# Debug.net
KiCad netlist of a schematic drawn in Altium Designer
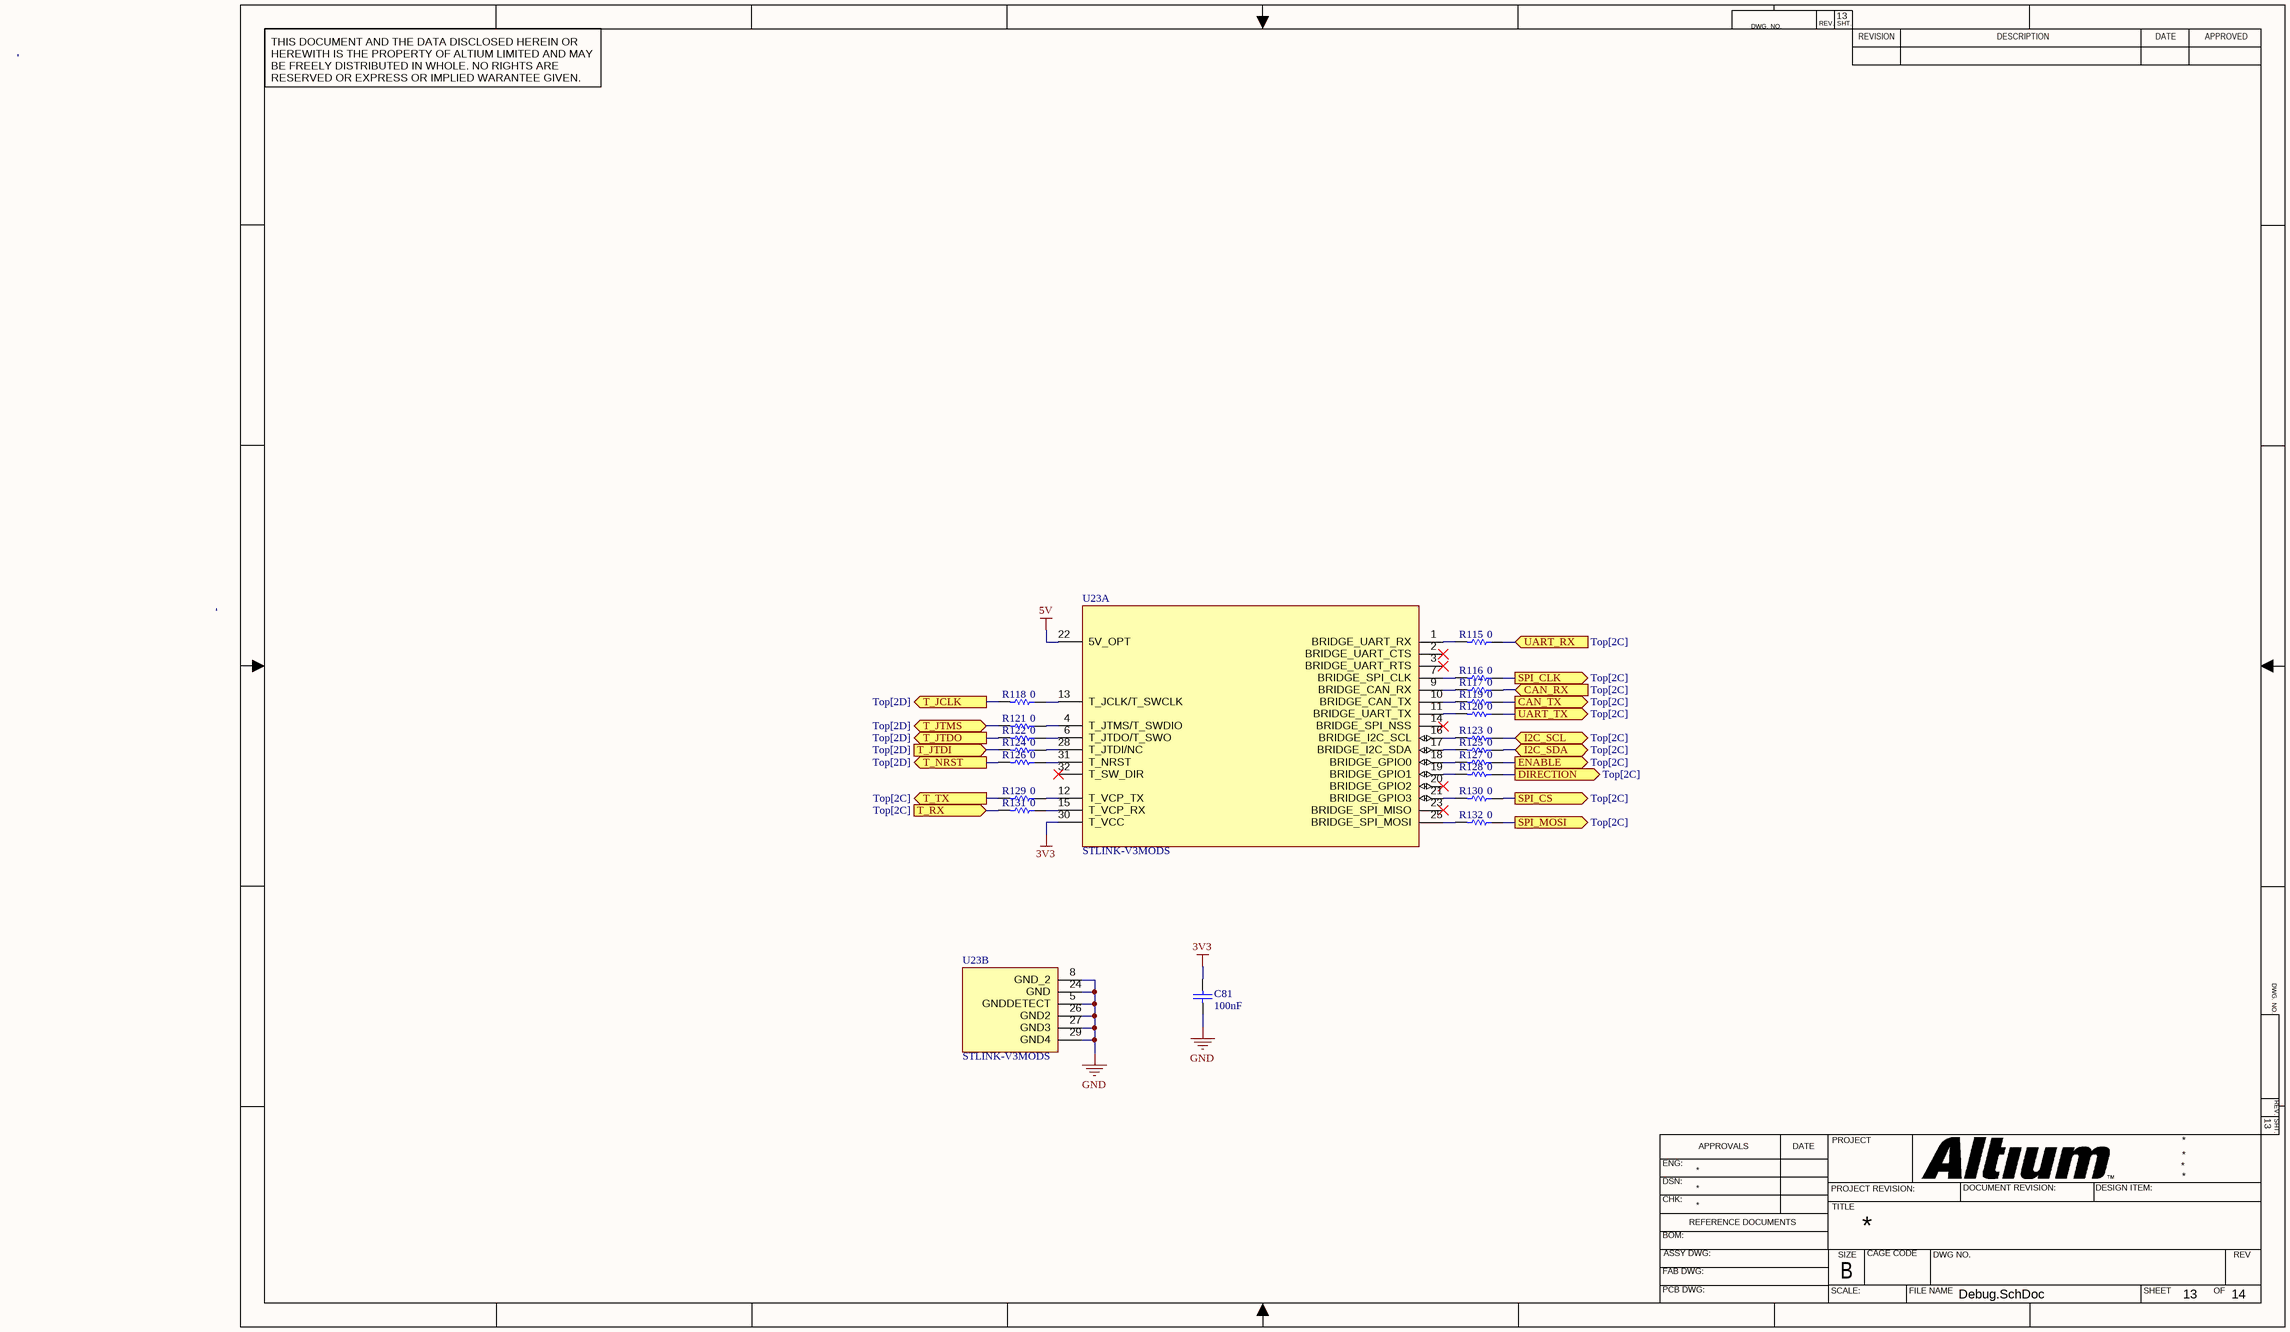
[diagram p0: Debug.SchDoc]

(export (version "E")
  (design (tool "Eeschema 10.0.6"))
  (components
    (comp (ref "C81")
      (value "100nF")
      (description "Capacitor")
      (libsource (lib "Simulation Generic Components") (part "Capacitor"))
    )
    (comp (ref "R115")
      (value "0")
      (description "Resistor")
      (libsource (lib "Simulation Generic Components") (part "Resistor"))
    )
    (comp (ref "R116")
      (value "0")
      (description "Resistor")
      (libsource (lib "Simulation Generic Components") (part "Resistor"))
    )
    (comp (ref "R117")
      (value "0")
      (description "Resistor")
      (libsource (lib "Simulation Generic Components") (part "Resistor"))
    )
    (comp (ref "R118")
      (value "0")
      (description "Resistor")
      (libsource (lib "Simulation Generic Components") (part "Resistor"))
    )
    (comp (ref "R119")
      (value "0")
      (description "Resistor")
      (libsource (lib "Simulation Generic Components") (part "Resistor"))
    )
    (comp (ref "R120")
      (value "0")
      (description "Resistor")
      (libsource (lib "Simulation Generic Components") (part "Resistor"))
    )
    (comp (ref "R121")
      (value "0")
      (description "Resistor")
      (libsource (lib "Simulation Generic Components") (part "Resistor"))
    )
    (comp (ref "R122")
      (value "0")
      (description "Resistor")
      (libsource (lib "Simulation Generic Components") (part "Resistor"))
    )
    (comp (ref "R123")
      (value "0")
      (description "Resistor")
      (libsource (lib "Simulation Generic Components") (part "Resistor"))
    )
    (comp (ref "R124")
      (value "0")
      (description "Resistor")
      (libsource (lib "Simulation Generic Components") (part "Resistor"))
    )
    (comp (ref "R125")
      (value "0")
      (description "Resistor")
      (libsource (lib "Simulation Generic Components") (part "Resistor"))
    )
    (comp (ref "R126")
      (value "0")
      (description "Resistor")
      (libsource (lib "Simulation Generic Components") (part "Resistor"))
    )
    (comp (ref "R127")
      (value "0")
      (description "Resistor")
      (libsource (lib "Simulation Generic Components") (part "Resistor"))
    )
    (comp (ref "R128")
      (value "0")
      (description "Resistor")
      (libsource (lib "Simulation Generic Components") (part "Resistor"))
    )
    (comp (ref "R129")
      (value "0")
      (description "Resistor")
      (libsource (lib "Simulation Generic Components") (part "Resistor"))
    )
    (comp (ref "R130")
      (value "0")
      (description "Resistor")
      (libsource (lib "Simulation Generic Components") (part "Resistor"))
    )
    (comp (ref "R131")
      (value "0")
      (description "Resistor")
      (libsource (lib "Simulation Generic Components") (part "Resistor"))
    )
    (comp (ref "R132")
      (value "0")
      (description "Resistor")
      (libsource (lib "Simulation Generic Components") (part "Resistor"))
    )
    (comp (ref "U23")
      (value "STLINK-V3MODS")
      (footprint "MODULE_STLINK-V3MODS")
      (libsource (lib "GSSM Golf Cart") (part "STLINK-V3MODS"))
    )
  )
  (nets
    (net (code "1") (name "/CAN_RX") (class "Default")
      (node (ref "R117") (pin "1") (pinfunction "1_1") (pintype "passive"))
    )
    (net (code "2") (name "/CAN_TX") (class "Default")
      (node (ref "R119") (pin "1") (pinfunction "1_1") (pintype "passive"))
    )
    (net (code "3") (name "/DIRECTION") (class "Default")
      (node (ref "R128") (pin "1") (pinfunction "1_1") (pintype "passive"))
    )
    (net (code "4") (name "/ENABLE") (class "Default")
      (node (ref "R127") (pin "1") (pinfunction "1_1") (pintype "passive"))
    )
    (net (code "5") (name "/I2C_SCL") (class "Default")
      (node (ref "R123") (pin "1") (pinfunction "1_1") (pintype "passive"))
    )
    (net (code "6") (name "/I2C_SDA") (class "Default")
      (node (ref "R125") (pin "1") (pinfunction "1_1") (pintype "passive"))
    )
    (net (code "7") (name "/SPI_CLK") (class "Default")
      (node (ref "R116") (pin "1") (pinfunction "1_1") (pintype "passive"))
    )
    (net (code "8") (name "/SPI_CS") (class "Default")
      (node (ref "R130") (pin "1") (pinfunction "1_1") (pintype "passive"))
    )
    (net (code "9") (name "/SPI_MOSI") (class "Default")
      (node (ref "R132") (pin "1") (pinfunction "1_1") (pintype "passive"))
    )
    (net (code "10") (name "/T_JCLK") (class "Default")
      (node (ref "R118") (pin "2") (pinfunction "2_2") (pintype "passive"))
    )
    (net (code "11") (name "/T_JTDI") (class "Default")
      (node (ref "R124") (pin "2") (pinfunction "2_2") (pintype "passive"))
    )
    (net (code "12") (name "/T_JTDO") (class "Default")
      (node (ref "R122") (pin "2") (pinfunction "2_2") (pintype "passive"))
    )
    (net (code "13") (name "/T_JTMS") (class "Default")
      (node (ref "R121") (pin "2") (pinfunction "2_2") (pintype "passive"))
    )
    (net (code "14") (name "/T_NRST") (class "Default")
      (node (ref "R126") (pin "2") (pinfunction "2_2") (pintype "passive"))
    )
    (net (code "15") (name "/T_RX") (class "Default")
      (node (ref "R131") (pin "2") (pinfunction "2_2") (pintype "passive"))
    )
    (net (code "16") (name "/T_TX") (class "Default")
      (node (ref "R129") (pin "2") (pinfunction "2_2") (pintype "passive"))
    )
    (net (code "17") (name "/UART_RX") (class "Default")
      (node (ref "R115") (pin "1") (pinfunction "1_1") (pintype "passive"))
    )
    (net (code "18") (name "/UART_TX") (class "Default")
      (node (ref "R120") (pin "1") (pinfunction "1_1") (pintype "passive"))
    )
    (net (code "19") (name "3V3") (class "Default")
      (node (ref "C81") (pin "2") (pinfunction "2_2") (pintype "passive"))
      (node (ref "U23") (pin "30") (pinfunction "T_VCC_30") (pintype "passive"))
    )
    (net (code "20") (name "5V") (class "Default")
      (node (ref "U23") (pin "22") (pinfunction "5V_OPT_22") (pintype "passive"))
    )
    (net (code "21") (name "GND") (class "Default")
      (node (ref "C81") (pin "1") (pinfunction "1_1") (pintype "passive"))
      (node (ref "U23") (pin "24") (pinfunction "GND_24") (pintype "power_in"))
      (node (ref "U23") (pin "26") (pinfunction "GND2_26") (pintype "power_in"))
      (node (ref "U23") (pin "27") (pinfunction "GND3_27") (pintype "power_in"))
      (node (ref "U23") (pin "29") (pinfunction "GND4_29") (pintype "power_in"))
      (node (ref "U23") (pin "5") (pinfunction "GNDDETECT_5") (pintype "power_in"))
      (node (ref "U23") (pin "8") (pinfunction "GND_2_8") (pintype "power_in"))
    )
    (net (code "22") (name "Net-(U23A-BRIDGE_CAN_RX)") (class "Default")
      (node (ref "R117") (pin "2") (pinfunction "2_2") (pintype "passive"))
      (node (ref "U23") (pin "9") (pinfunction "BRIDGE_CAN_RX_9") (pintype "passive"))
    )
    (net (code "23") (name "Net-(U23A-BRIDGE_CAN_TX)") (class "Default")
      (node (ref "R119") (pin "2") (pinfunction "2_2") (pintype "passive"))
      (node (ref "U23") (pin "10") (pinfunction "BRIDGE_CAN_TX_10") (pintype "passive"))
    )
    (net (code "24") (name "Net-(U23A-BRIDGE_GPIO0)") (class "Default")
      (node (ref "R127") (pin "2") (pinfunction "2_2") (pintype "passive"))
      (node (ref "U23") (pin "18") (pinfunction "BRIDGE_GPIO0_18") (pintype "bidirectional"))
    )
    (net (code "25") (name "Net-(U23A-BRIDGE_GPIO1)") (class "Default")
      (node (ref "R128") (pin "2") (pinfunction "2_2") (pintype "passive"))
      (node (ref "U23") (pin "19") (pinfunction "BRIDGE_GPIO1_19") (pintype "bidirectional"))
    )
    (net (code "26") (name "Net-(U23A-BRIDGE_GPIO3)") (class "Default")
      (node (ref "R130") (pin "2") (pinfunction "2_2") (pintype "passive"))
      (node (ref "U23") (pin "21") (pinfunction "BRIDGE_GPIO3_21") (pintype "bidirectional"))
    )
    (net (code "27") (name "Net-(U23A-BRIDGE_I2C_SCL)") (class "Default")
      (node (ref "R123") (pin "2") (pinfunction "2_2") (pintype "passive"))
      (node (ref "U23") (pin "16") (pinfunction "BRIDGE_I2C_SCL_16") (pintype "bidirectional"))
    )
    (net (code "28") (name "Net-(U23A-BRIDGE_I2C_SDA)") (class "Default")
      (node (ref "R125") (pin "2") (pinfunction "2_2") (pintype "passive"))
      (node (ref "U23") (pin "17") (pinfunction "BRIDGE_I2C_SDA_17") (pintype "bidirectional"))
    )
    (net (code "29") (name "Net-(U23A-BRIDGE_SPI_CLK)") (class "Default")
      (node (ref "R116") (pin "2") (pinfunction "2_2") (pintype "passive"))
      (node (ref "U23") (pin "7") (pinfunction "BRIDGE_SPI_CLK_7") (pintype "passive"))
    )
    (net (code "30") (name "Net-(U23A-BRIDGE_SPI_MOSI)") (class "Default")
      (node (ref "R132") (pin "2") (pinfunction "2_2") (pintype "passive"))
      (node (ref "U23") (pin "25") (pinfunction "BRIDGE_SPI_MOSI_25") (pintype "passive"))
    )
    (net (code "31") (name "Net-(U23A-BRIDGE_UART_RX)") (class "Default")
      (node (ref "R115") (pin "2") (pinfunction "2_2") (pintype "passive"))
      (node (ref "U23") (pin "1") (pinfunction "BRIDGE_UART_RX_1") (pintype "passive"))
    )
    (net (code "32") (name "Net-(U23A-BRIDGE_UART_TX)") (class "Default")
      (node (ref "R120") (pin "2") (pinfunction "2_2") (pintype "passive"))
      (node (ref "U23") (pin "11") (pinfunction "BRIDGE_UART_TX_11") (pintype "passive"))
    )
    (net (code "33") (name "Net-(U23A-T_JCLK{slash}T_SWCLK)") (class "Default")
      (node (ref "R118") (pin "1") (pinfunction "1_1") (pintype "passive"))
      (node (ref "U23") (pin "13") (pinfunction "T_JCLK/T_SWCLK_13") (pintype "passive"))
    )
    (net (code "34") (name "Net-(U23A-T_JTDI{slash}NC)") (class "Default")
      (node (ref "R124") (pin "1") (pinfunction "1_1") (pintype "passive"))
      (node (ref "U23") (pin "28") (pinfunction "T_JTDI/NC_28") (pintype "passive"))
    )
    (net (code "35") (name "Net-(U23A-T_JTDO{slash}T_SWO)") (class "Default")
      (node (ref "R122") (pin "1") (pinfunction "1_1") (pintype "passive"))
      (node (ref "U23") (pin "6") (pinfunction "T_JTDO/T_SWO_6") (pintype "passive"))
    )
    (net (code "36") (name "Net-(U23A-T_JTMS{slash}T_SWDIO)") (class "Default")
      (node (ref "R121") (pin "1") (pinfunction "1_1") (pintype "passive"))
      (node (ref "U23") (pin "4") (pinfunction "T_JTMS/T_SWDIO_4") (pintype "passive"))
    )
    (net (code "37") (name "Net-(U23A-T_NRST)") (class "Default")
      (node (ref "R126") (pin "1") (pinfunction "1_1") (pintype "passive"))
      (node (ref "U23") (pin "31") (pinfunction "T_NRST_31") (pintype "passive"))
    )
    (net (code "38") (name "Net-(U23A-T_VCP_RX)") (class "Default")
      (node (ref "R131") (pin "1") (pinfunction "1_1") (pintype "passive"))
      (node (ref "U23") (pin "15") (pinfunction "T_VCP_RX_15") (pintype "passive"))
    )
    (net (code "39") (name "Net-(U23A-T_VCP_TX)") (class "Default")
      (node (ref "R129") (pin "1") (pinfunction "1_1") (pintype "passive"))
      (node (ref "U23") (pin "12") (pinfunction "T_VCP_TX_12") (pintype "passive"))
    )
    (net (code "40") (name "unconnected-(U23A-BRIDGE_GPIO2-Pad20)") (class "Default")
      (node (ref "U23") (pin "20") (pinfunction "BRIDGE_GPIO2_20") (pintype "bidirectional+no_connect"))
    )
    (net (code "41") (name "unconnected-(U23A-BRIDGE_SPI_MISO-Pad23)") (class "Default")
      (node (ref "U23") (pin "23") (pinfunction "BRIDGE_SPI_MISO_23") (pintype "passive+no_connect"))
    )
    (net (code "42") (name "unconnected-(U23A-BRIDGE_SPI_NSS-Pad14)") (class "Default")
      (node (ref "U23") (pin "14") (pinfunction "BRIDGE_SPI_NSS_14") (pintype "passive+no_connect"))
    )
    (net (code "43") (name "unconnected-(U23A-BRIDGE_UART_CTS-Pad2)") (class "Default")
      (node (ref "U23") (pin "2") (pinfunction "BRIDGE_UART_CTS_2") (pintype "passive+no_connect"))
    )
    (net (code "44") (name "unconnected-(U23A-BRIDGE_UART_RTS-Pad3)") (class "Default")
      (node (ref "U23") (pin "3") (pinfunction "BRIDGE_UART_RTS_3") (pintype "passive+no_connect"))
    )
    (net (code "45") (name "unconnected-(U23A-T_SW_DIR-Pad32)") (class "Default")
      (node (ref "U23") (pin "32") (pinfunction "T_SW_DIR_32") (pintype "passive+no_connect"))
    )
  )
)
